# ProDoc_Board3_2025-07-21.net
KiCad netlist of a schematic drawn in EasyEDA Pro
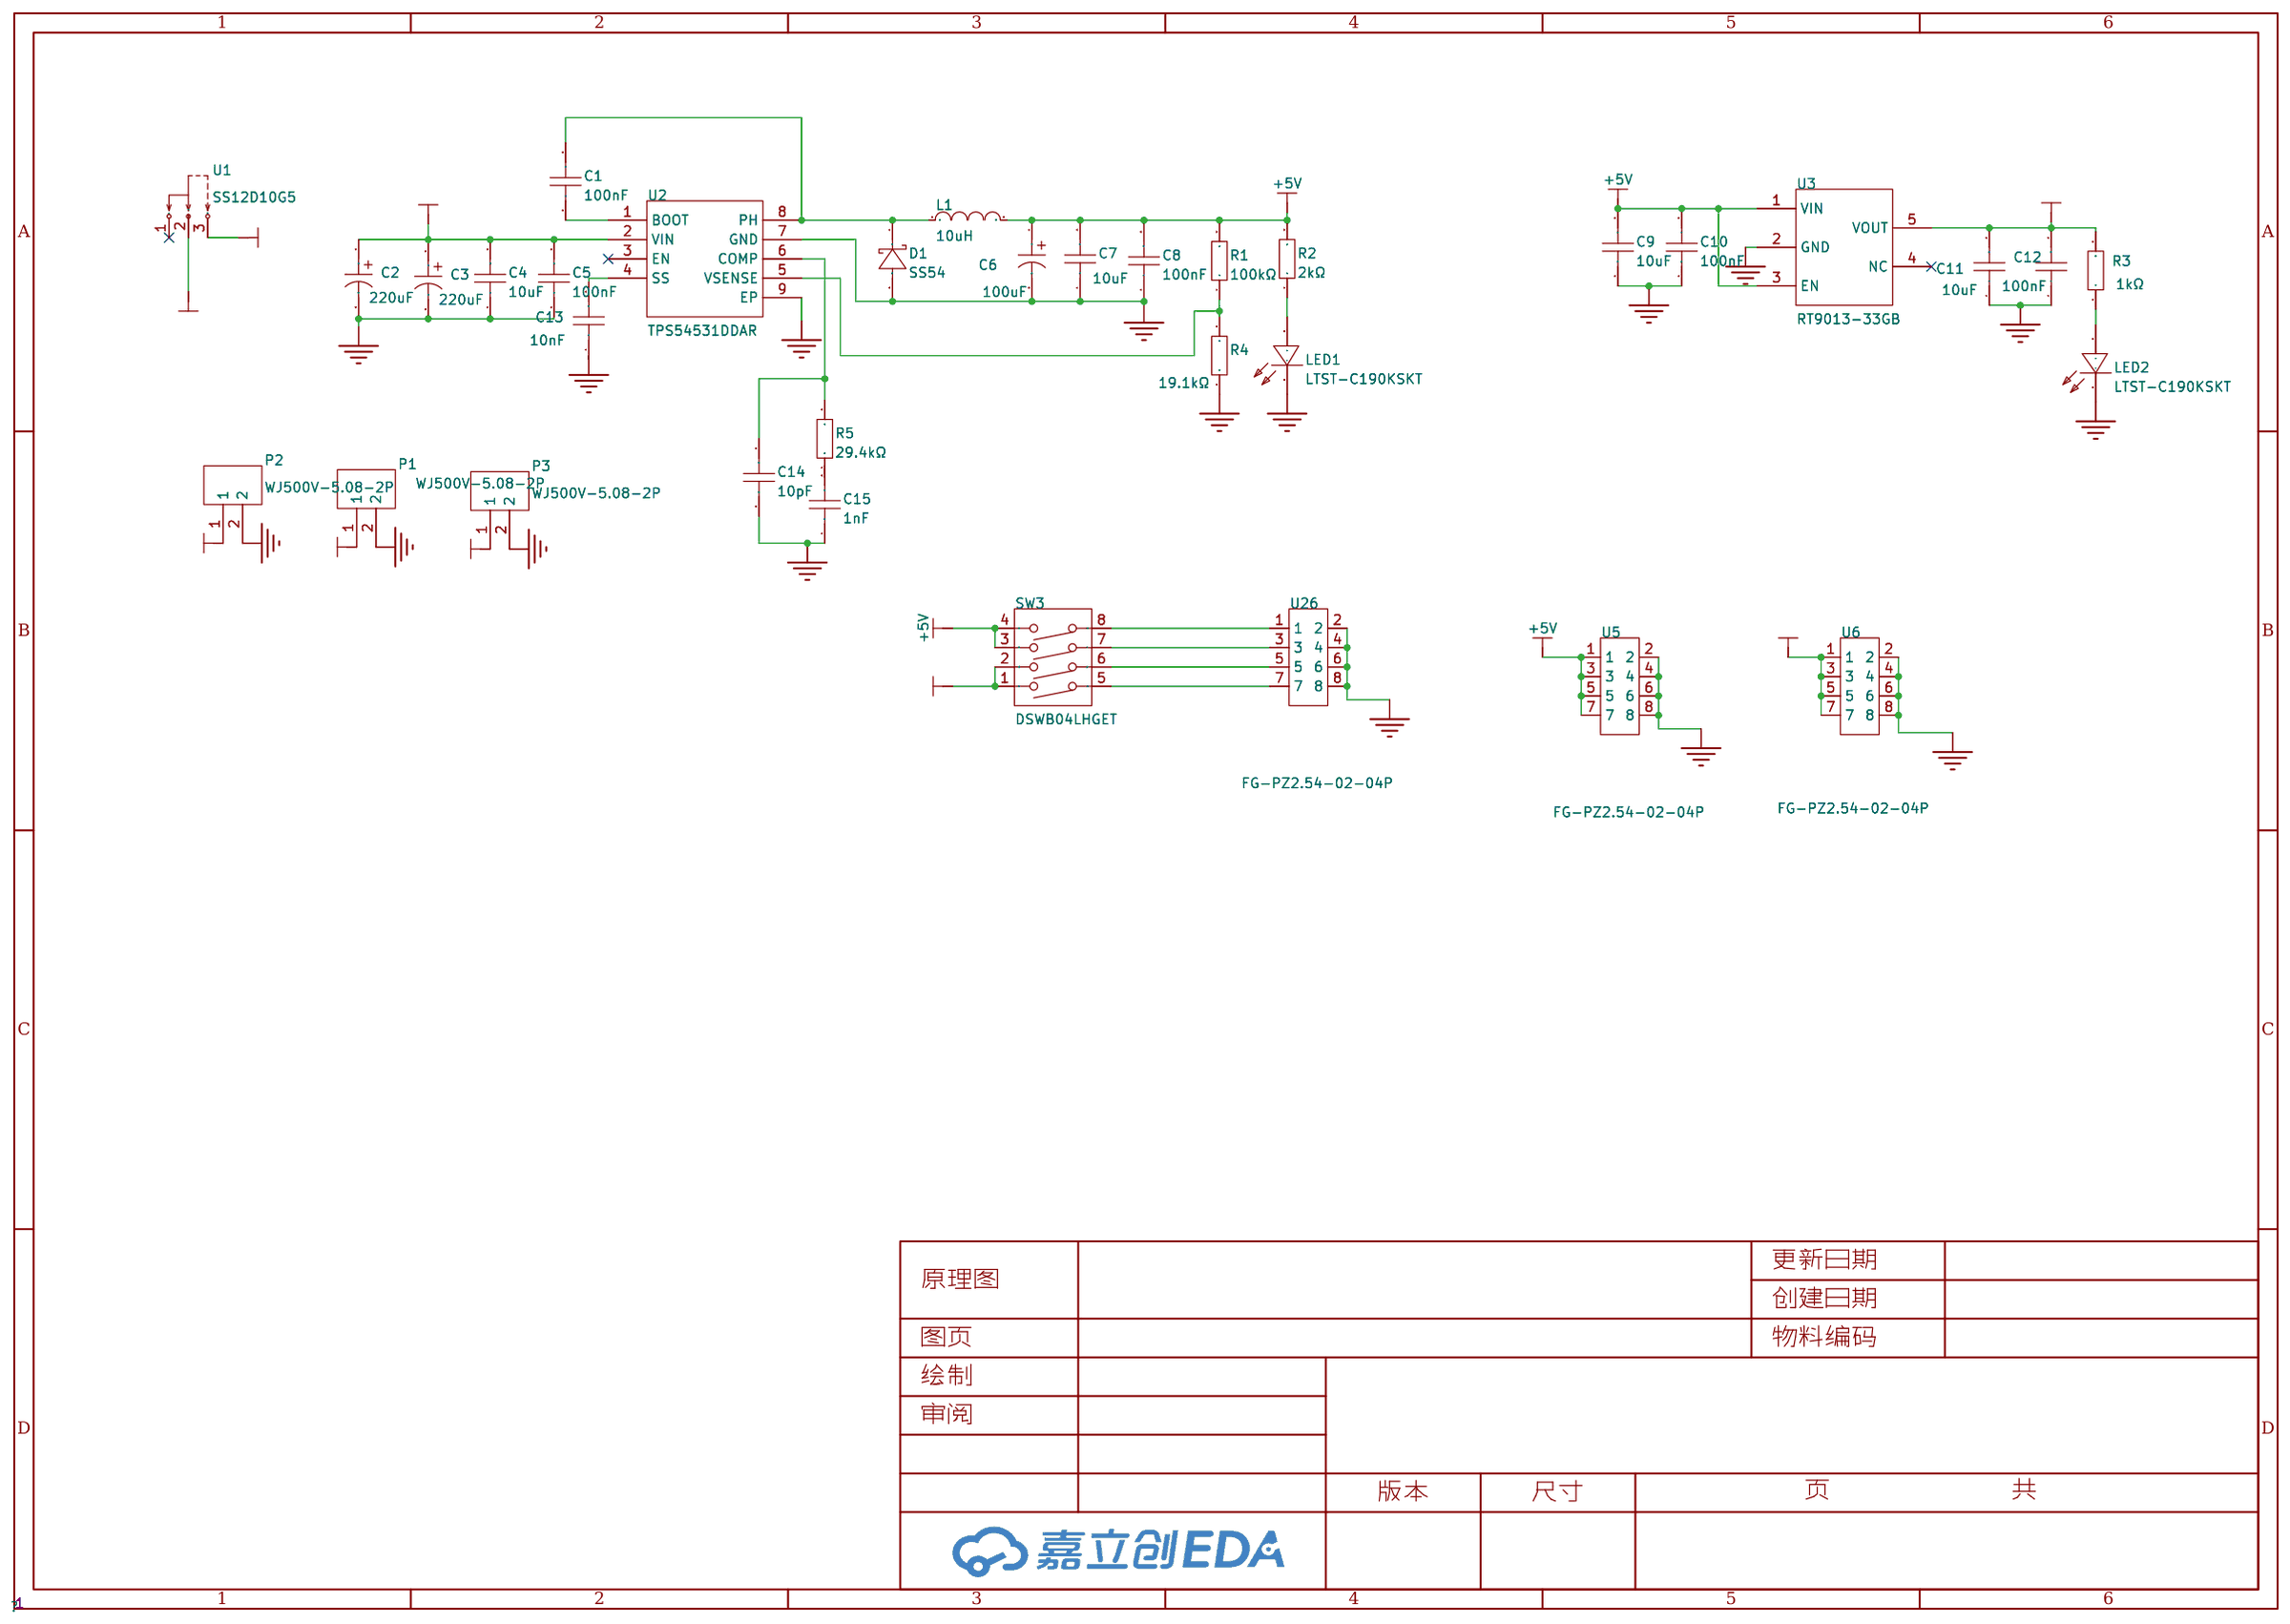
[diagram p0: POWER]
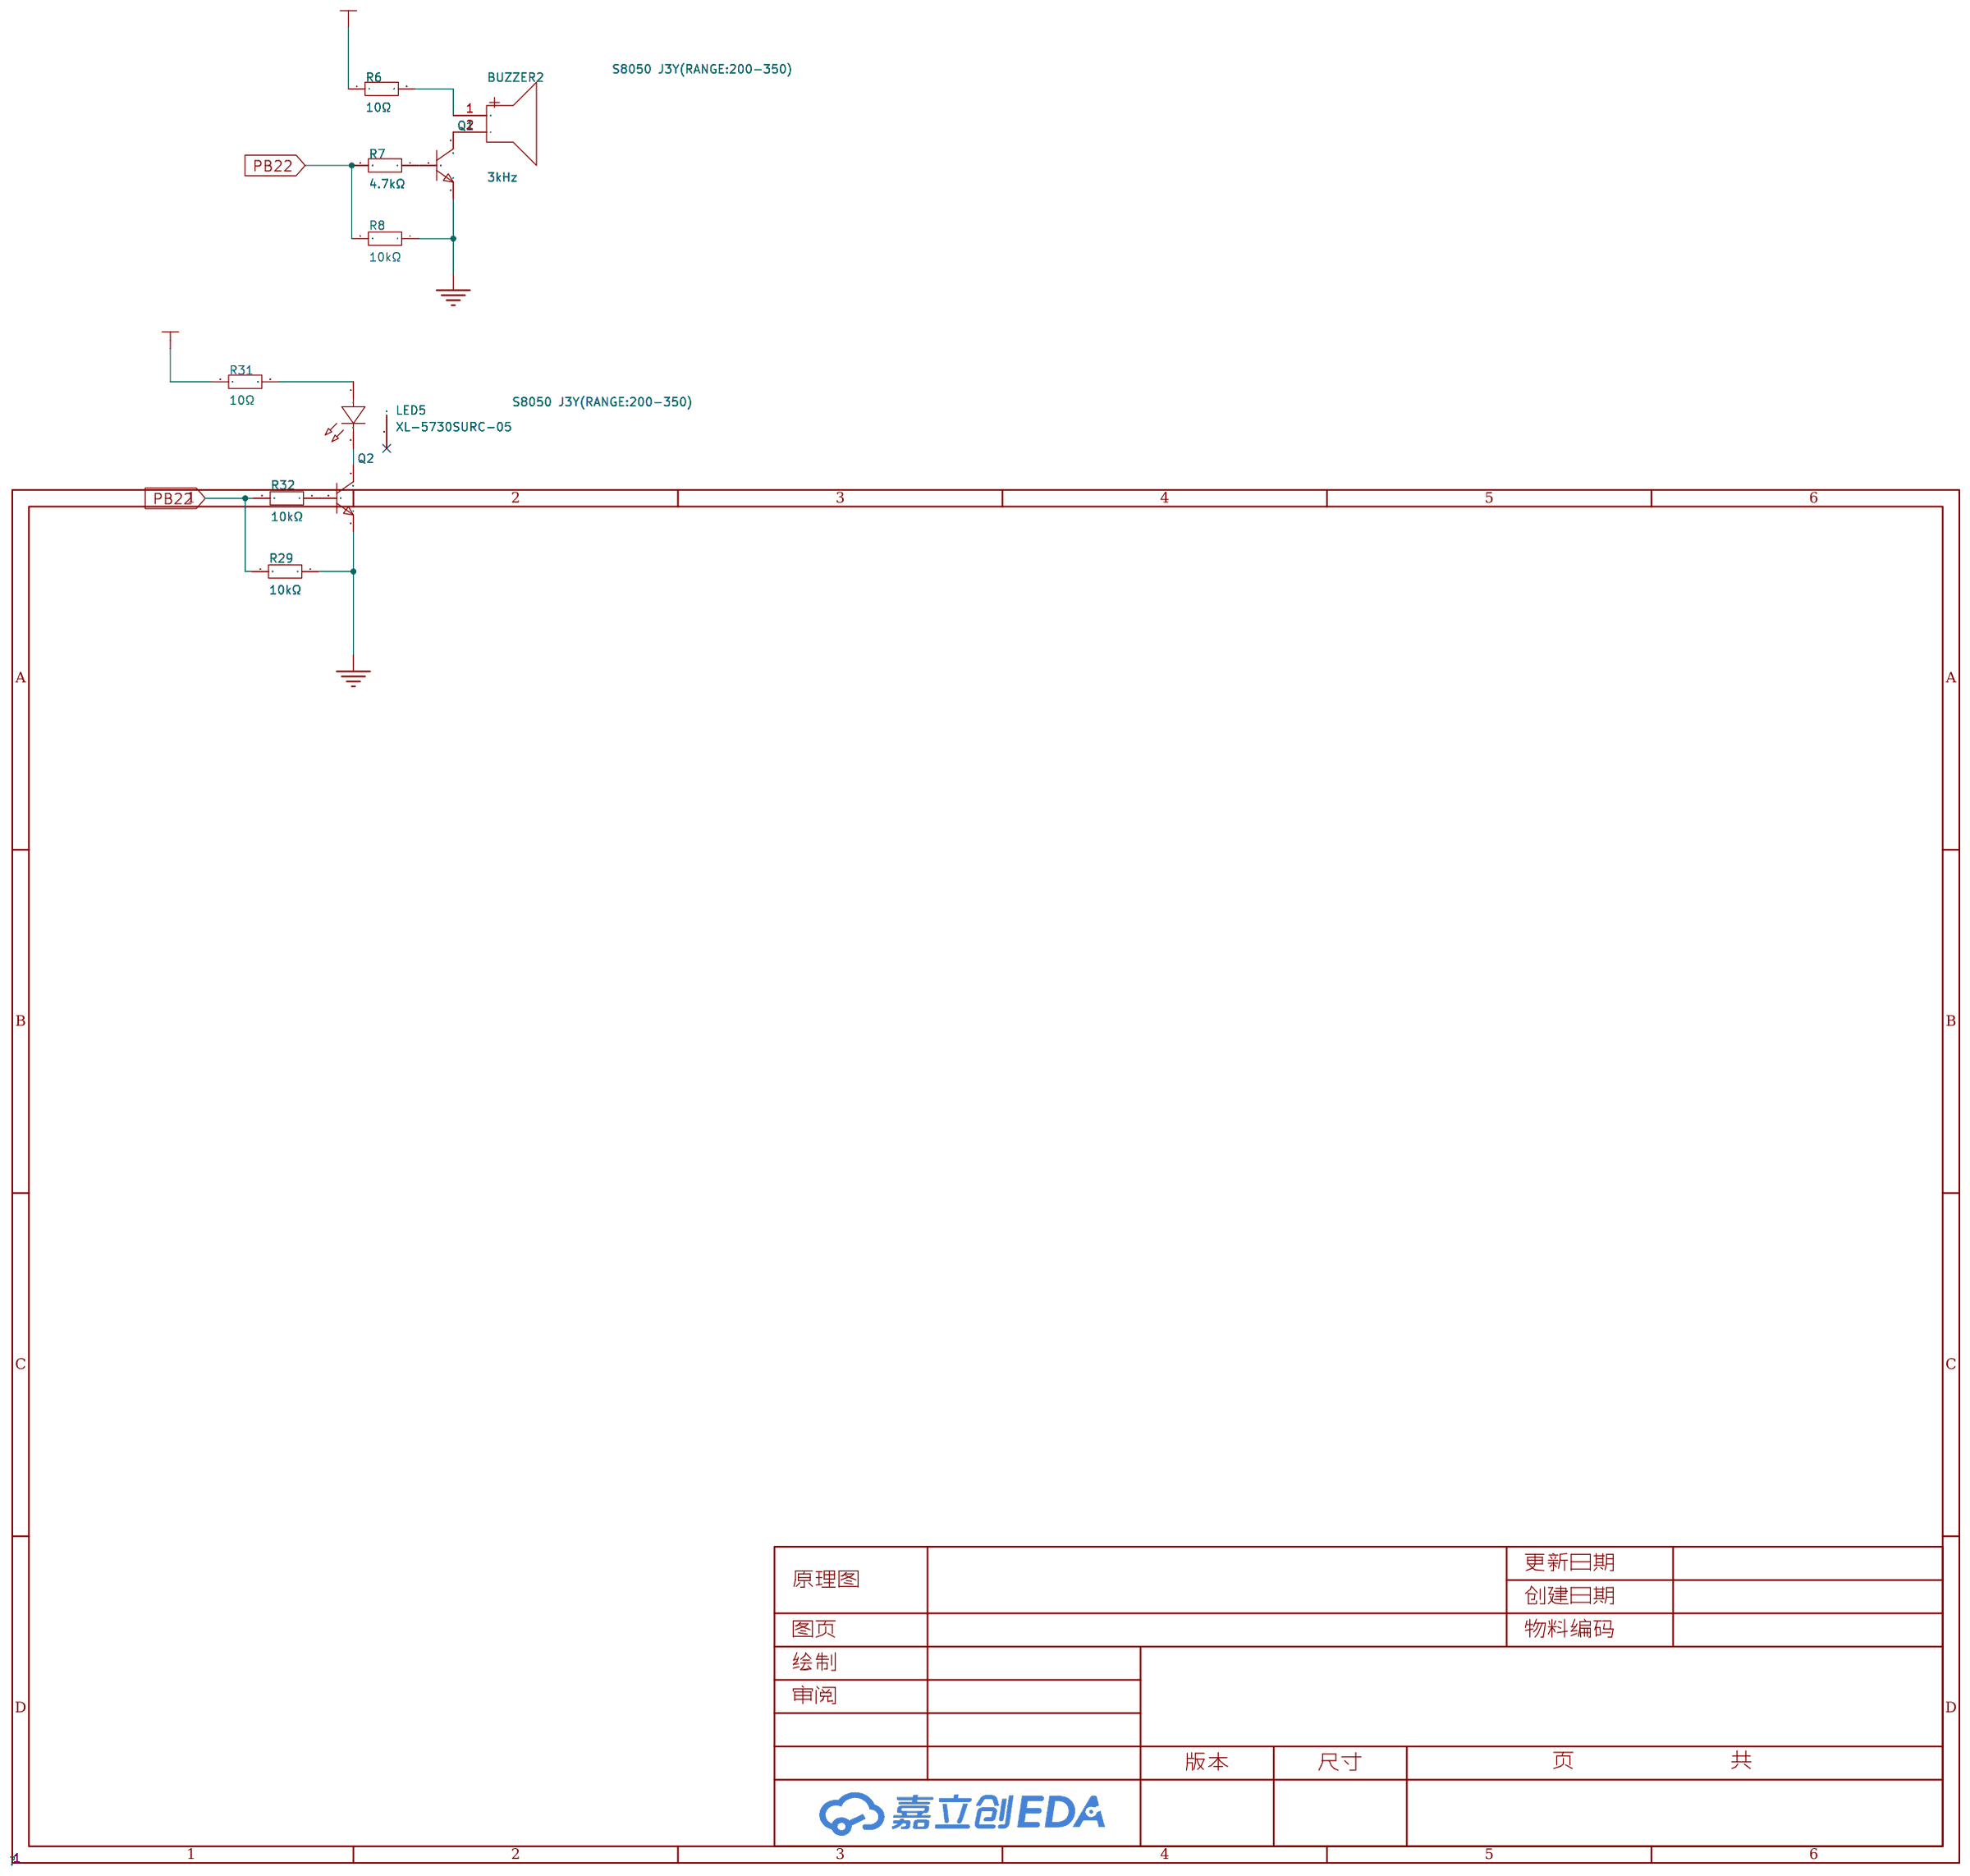
[diagram p1: 器件]
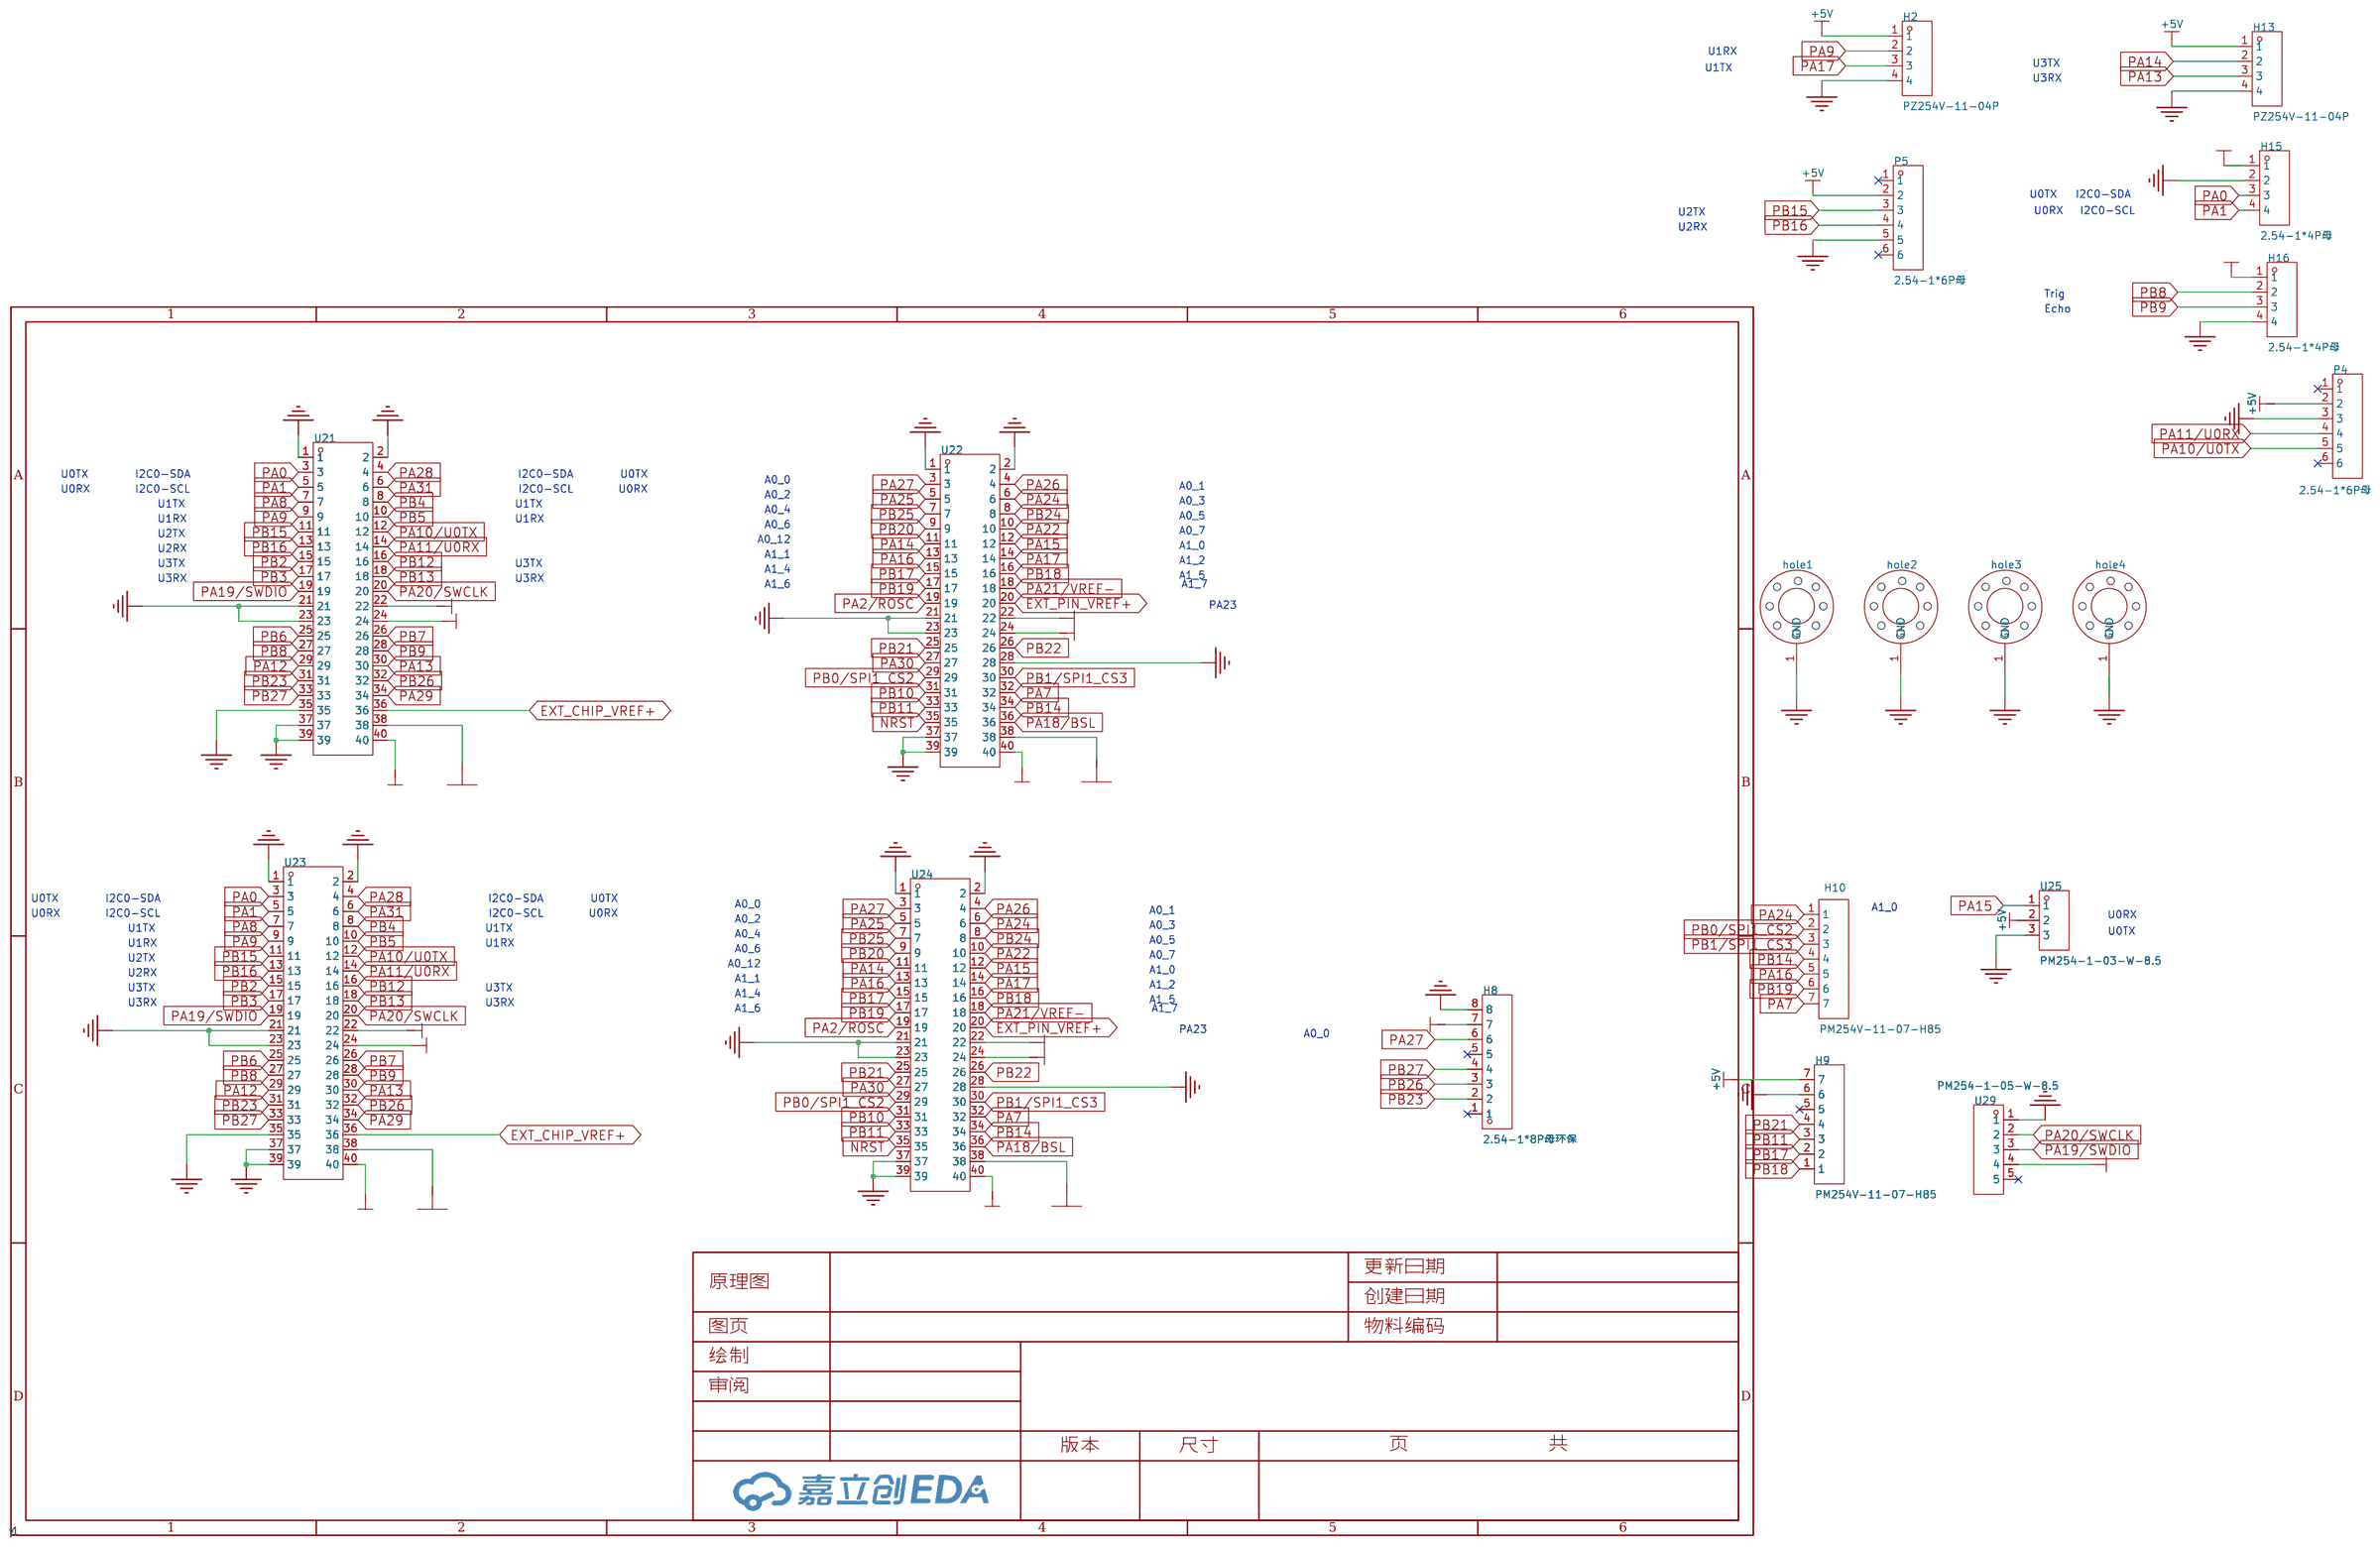
[diagram p2: 连接]

(export (version "E")
  (design (tool "Eeschema 10.0.6"))
  (components
    (comp (ref "C1")
      (value "100nF")
      (fields
        (field (name "Manufacturer Part") "CC0603KRX7R9BB104")
        (field (name "Manufacturer") "YAGEO(国巨)")
      )
      (libsource (lib "easyedapro") (part "CapAcitance"))
    )
    (comp (ref "C2")
      (value "220uF")
      (footprint "easyedapro:CAP-SMD_BD6.3-L6.6-W6.6-LS7.4-FD")
      (description "容值:220uF;精度:±20%;额定电压:25V;纹波电流:150mA@120Hz;等效串联电阻(ESR):-;")
      (fields (field (name "Manufacturer Part") "RVT1E221M0607") (field (name "Manufacturer") "ROQANG(容强)"))
      (libsource (lib "easyedapro") (part "RVT1E221M0607_C2918361"))
    )
    (comp (ref "C3")
      (value "220uF")
      (footprint "easyedapro:CAP-SMD_BD6.3-L6.6-W6.6-LS7.4-FD")
      (description "容值:220uF;精度:±20%;额定电压:25V;纹波电流:150mA@120Hz;等效串联电阻(ESR):-;")
      (fields (field (name "Manufacturer Part") "RVT1E221M0607") (field (name "Manufacturer") "ROQANG(容强)"))
      (libsource (lib "easyedapro") (part "RVT1E221M0607_C2918361"))
    )
    (comp (ref "C4")
      (value "10uF")
      (fields
        (field (name "Manufacturer Part") "CL21A106KAYNNNE")
        (field (name "Manufacturer") "SAMSUNG(三星)")
      )
      (libsource (lib "easyedapro") (part "CapAcitance"))
    )
    (comp (ref "C5")
      (value "100nF")
      (fields
        (field (name "Manufacturer Part") "CC0603KRX7R9BB104")
        (field (name "Manufacturer") "YAGEO(国巨)")
      )
      (libsource (lib "easyedapro") (part "CapAcitance"))
    )
    (comp (ref "C6")
      (value "100uF")
      (footprint "easyedapro:CAP-SMD_BD6.3-L6.6-W6.6-LS7.6-RD")
      (description "容值:100uF;精度:±20%;额定电压:50V;纹波电流:229mA@120Hz;")
      (fields (field (name "Manufacturer Part") "RVT1H101M0607") (field (name "Manufacturer") "ROQANG(容强)"))
      (libsource (lib "easyedapro") (part "RVT1H101M0607"))
    )
    (comp (ref "C7")
      (value "10uF")
      (fields
        (field (name "Manufacturer Part") "CL21A106KAYNNNE")
        (field (name "Manufacturer") "SAMSUNG(三星)")
      )
      (libsource (lib "easyedapro") (part "CapAcitance"))
    )
    (comp (ref "C8")
      (value "100nF")
      (fields
        (field (name "Manufacturer Part") "CC0603KRX7R9BB104")
        (field (name "Manufacturer") "YAGEO(国巨)")
      )
      (libsource (lib "easyedapro") (part "CapAcitance"))
    )
    (comp (ref "C9")
      (value "10uF")
      (fields
        (field (name "Manufacturer Part") "CL21A106KAYNNNE")
        (field (name "Manufacturer") "SAMSUNG(三星)")
      )
      (libsource (lib "easyedapro") (part "CapAcitance"))
    )
    (comp (ref "C10")
      (value "100nF")
      (fields
        (field (name "Manufacturer Part") "CC0603KRX7R9BB104")
        (field (name "Manufacturer") "YAGEO(国巨)")
      )
      (libsource (lib "easyedapro") (part "CapAcitance"))
    )
    (comp (ref "C11")
      (value "10uF")
      (fields
        (field (name "Manufacturer Part") "CL21A106KAYNNNE")
        (field (name "Manufacturer") "SAMSUNG(三星)")
      )
      (libsource (lib "easyedapro") (part "CapAcitance"))
    )
    (comp (ref "C12")
      (value "100nF")
      (fields
        (field (name "Manufacturer Part") "CC0603KRX7R9BB104")
        (field (name "Manufacturer") "YAGEO(国巨)")
      )
      (libsource (lib "easyedapro") (part "CapAcitance"))
    )
    (comp (ref "C13")
      (value "10nF")
      (fields (field (name "Manufacturer Part") "0603B103K500NT") (field (name "Manufacturer") "FH(风华)"))
      (libsource (lib "easyedapro") (part "CapAcitance"))
    )
    (comp (ref "C14")
      (value "10pF")
      (fields
        (field (name "Manufacturer Part") "CL10C100JB8NNNC")
        (field (name "Manufacturer") "SAMSUNG(三星)")
      )
      (libsource (lib "easyedapro") (part "CapAcitance"))
    )
    (comp (ref "C15")
      (value "1nF")
      (fields
        (field (name "Manufacturer Part") "CL10B102KB8NNNC")
        (field (name "Manufacturer") "SAMSUNG(三星)")
      )
      (libsource (lib "easyedapro") (part "CapAcitance"))
    )
    (comp (ref "D1")
      (value "SS54")
      (footprint "easyedapro:SMA_L4.3-W2.6-LS5.0-RD")
      (description "二极管配置:独立式;正向压降(Vf):550mV@5A;直流反向耐压(Vr):40V;整流电流:5A;")
      (fields (field (name "Manufacturer") "TWGMC(台湾迪嘉)"))
      (libsource (lib "easyedapro") (part "SS54_C727065"))
    )
    (comp (ref "L1")
      (value "10uH")
      (footprint "easyedapro:IND-SMD_L7.3-W6.6")
      (description "电感值:10uH;精度:±20%;额定电流:-;饱和电流(Isat):5.5A;类型:一体成型电感;")
      (fields (field (name "Manufacturer Part") "SMMS0630-100M") (field (name "Manufacturer") "SXN(顺翔诺)"))
      (libsource (lib "easyedapro") (part "SMMS0630-100M"))
    )
    (comp (ref "LED1")
      (value "LTST-C190KSKT")
      (footprint "easyedapro:LED0603-RD")
      (fields (field (name "Manufacturer") "LITEON(光宝)"))
      (libsource (lib "easyedapro") (part "LTST-C190KSKT"))
    )
    (comp (ref "LED2")
      (value "LTST-C190KSKT")
      (footprint "easyedapro:LED0603-RD")
      (fields (field (name "Manufacturer") "LITEON(光宝)"))
      (libsource (lib "easyedapro") (part "LTST-C190KSKT"))
    )
    (comp (ref "P1")
      (value "WJ500V-5.08-2P")
      (footprint "easyedapro:CONN-TH_2P-P5.00_WJ500V-5.08-2P")
      (fields (field (name "Manufacturer") "KANGNEX(康奈克斯电气)"))
      (libsource (lib "easyedapro") (part "WJ500V-5.08-2P-14-00A"))
    )
    (comp (ref "P2")
      (value "WJ500V-5.08-2P")
      (footprint "easyedapro:CONN-TH_2P-P5.00_WJ500V-5.08-2P")
      (fields (field (name "Manufacturer") "KANGNEX(康奈克斯电气)"))
      (libsource (lib "easyedapro") (part "WJ500V-5.08-2P-14-00A"))
    )
    (comp (ref "P3")
      (value "WJ500V-5.08-2P")
      (footprint "easyedapro:CONN-TH_2P-P5.00_WJ500V-5.08-2P")
      (fields (field (name "Manufacturer") "KANGNEX(康奈克斯电气)"))
      (libsource (lib "easyedapro") (part "WJ500V-5.08-2P-14-00A"))
    )
    (comp (ref "R1")
      (value "100kΩ")
      (fields
        (field (name "Manufacturer Part") "0603WAF1003T5E")
        (field (name "Manufacturer") "UNI-ROYAL(厚声)")
      )
      (libsource (lib "easyedapro") (part "电阻"))
    )
    (comp (ref "R2")
      (value "2kΩ")
      (fields
        (field (name "Manufacturer Part") "0603WAF2001T5E")
        (field (name "Manufacturer") "UNI-ROYAL(厚声)")
      )
      (libsource (lib "easyedapro") (part "电阻"))
    )
    (comp (ref "R3")
      (value "1kΩ")
      (fields
        (field (name "Manufacturer Part") "0603WAF1001T5E")
        (field (name "Manufacturer") "UNI-ROYAL(厚声)")
      )
      (libsource (lib "easyedapro") (part "电阻"))
    )
    (comp (ref "R4")
      (value "19.1kΩ")
      (fields
        (field (name "Manufacturer Part") "0603WAF1912T5E")
        (field (name "Manufacturer") "UNI-ROYAL(厚声)")
      )
      (libsource (lib "easyedapro") (part "电阻"))
    )
    (comp (ref "R5")
      (value "29.4kΩ")
      (fields (field (name "Manufacturer Part") "FRC0603F2942TS") (field (name "Manufacturer") "FOJAN(富捷)"))
      (libsource (lib "easyedapro") (part "电阻"))
    )
    (comp (ref "SW3")
      (value "DSWB04LHGET")
      (footprint "easyedapro:SW-TH_DSWB04LHGET")
      (description "类型:平拨,凸起式;电路结构:单刀单掷;开关位数:4位;使用寿命:-;颜色:红色;")
      (fields (field (name "Manufacturer") "YE"))
      (libsource (lib "easyedapro") (part "DSWB04LHGET"))
    )
    (comp (ref "U1")
      (value "SS12D10G5")
      (footprint "easyedapro:SW-TH_SHOU-HAN_SS12D10G4")
      (description "电路结构:单刀双掷;安装方式:直插;额定电流(DC):2A;额定电压(DC):125V;机械寿命:3千次;")
      (fields (field (name "Manufacturer") "SHOU HAN(首韩)"))
      (libsource (lib "easyedapro") (part "SS12D10G5"))
    )
    (comp (ref "U2")
      (value "TPS54531DDAR")
      (footprint "easyedapro:SOIC-8_L5.0-W4.0-P1.27-LS6.0-BL-EP2.0")
      (description "功能类型:降压型;输出类型:可调;工作电压:3.5V~28V;输出电压:-;输出电流:5A;")
      (fields (field (name "Manufacturer") "TI(德州仪器)"))
      (libsource (lib "easyedapro") (part "TPS54531DDAR"))
    )
    (comp (ref "U3")
      (value "RT9013-33GB")
      (footprint "easyedapro:SOT-23-5_L3.0-W1.7-P0.95-LS2.8-BL")
      (description "输出类型:固定;最大输入电压:5.5V;输出电压:3.3V;输出电流:500mA;电源纹波抑制比(PSRR):50dB@(10kHz);输出极性:正极;")
      (fields (field (name "Manufacturer") "RICHTEK(立锜)"))
      (libsource (lib "easyedapro") (part "RT9013-33GB"))
    )
    (comp (ref "U5")
      (value "FG-PZ2.54-02-04P")
      (footprint "easyedapro:HDR-TH_8P-P2.54-V-M-R2-C4-S2.54")
      (description "插针结构:2x4P;间距:2.54mm;圆针/方针:方针;排数:双排;")
      (fields (field (name "Manufacturer") "FG(富港)"))
      (libsource (lib "easyedapro") (part "FG-PZ2.54-02-04P"))
    )
    (comp (ref "U6")
      (value "FG-PZ2.54-02-04P")
      (footprint "easyedapro:HDR-TH_8P-P2.54-V-M-R2-C4-S2.54")
      (description "插针结构:2x4P;间距:2.54mm;圆针/方针:方针;排数:双排;")
      (fields (field (name "Manufacturer") "FG(富港)"))
      (libsource (lib "easyedapro") (part "FG-PZ2.54-02-04P"))
    )
    (comp (ref "U26")
      (value "FG-PZ2.54-02-04P")
      (footprint "easyedapro:HDR-TH_8P-P2.54-V-M-R2-C4-S2.54")
      (description "插针结构:2x4P;间距:2.54mm;圆针/方针:方针;排数:双排;")
      (fields (field (name "Manufacturer") "FG(富港)"))
      (libsource (lib "easyedapro") (part "FG-PZ2.54-02-04P"))
    )
    (comp (ref "BUZZER2")
      (value "3kHz")
      (footprint "easyedapro:BUZ-TH_BD9.0-P5.00-D0.6-FD")
      (description "驱动方式:有源(内含驱动线路);构造类型:电磁式;频率:3kHz;声压(SPL):85dB;")
      (fields (field (name "Manufacturer Part") "HNB09A03") (field (name "Manufacturer") "华能"))
      (libsource (lib "easyedapro") (part "HNB09A03"))
    )
    (comp (ref "LED5")
      (value "XL-5730SURC-05")
      (footprint "easyedapro:LED-SMD_XL-5730SURC-05")
      (fields (field (name "Manufacturer") "XINGLIGHT(成兴光)"))
      (libsource (lib "easyedapro") (part "XL-5730SURC-05"))
    )
    (comp (ref "Q1")
      (value "S8050 J3Y(RANGE:200-350)")
      (footprint "easyedapro:SOT-23-3_L3.0-W1.7-P0.95-LS2.9-BR")
      (description "晶体管类型:NPN;集电极电流(Ic):500mA;集射极击穿电压(Vceo):25V;耗散功率(Pd):300mW;直流电流增益(hFE):200@500mA,1V;")
      (fields (field (name "Manufacturer") "CJ(江苏长电/长晶)"))
      (libsource (lib "easyedapro") (part "S8050_C2146"))
    )
    (comp (ref "Q2")
      (value "S8050 J3Y(RANGE:200-350)")
      (footprint "easyedapro:SOT-23-3_L3.0-W1.7-P0.95-LS2.9-BR")
      (description "晶体管类型:NPN;集电极电流(Ic):500mA;集射极击穿电压(Vceo):25V;耗散功率(Pd):300mW;直流电流增益(hFE):200@500mA,1V;")
      (fields (field (name "Manufacturer") "CJ(江苏长电/长晶)"))
      (libsource (lib "easyedapro") (part "S8050_C2146"))
    )
    (comp (ref "R6")
      (value "10Ω")
      (footprint "easyedapro:R0603")
      (description "电阻类型:厚膜电阻;阻值:10Ω;精度:±1%;功率:100mW;最大工作电压:75V;温度系数:±400ppm/°C;")
      (fields
        (field (name "Manufacturer Part") "0603WAF100JT5E")
        (field (name "Manufacturer") "UNI-ROYAL(厚声)")
      )
      (libsource (lib "easyedapro") (part "0603WAF100JT5E"))
    )
    (comp (ref "R7")
      (value "4.7kΩ")
      (footprint "easyedapro:R0603")
      (description "电阻类型:厚膜电阻;阻值:4.7kΩ;精度:±1%;功率:100mW;最大工作电压:75V;温度系数:±100ppm/°C;")
      (fields
        (field (name "Manufacturer Part") "0603WAF4701T5E")
        (field (name "Manufacturer") "UNI-ROYAL(厚声)")
      )
      (libsource (lib "easyedapro") (part "0603WAF4701T5E"))
    )
    (comp (ref "R8")
      (value "10kΩ")
      (footprint "easyedapro:R0603")
      (description "电阻类型:厚膜电阻;阻值:10kΩ;精度:±1%;功率:100mW;工作电压:75V;温度系数:±100ppm/℃;")
      (fields
        (field (name "Manufacturer Part") "0603WAF1002T5E")
        (field (name "Manufacturer") "UNI-ROYAL(厚声)")
      )
      (libsource (lib "easyedapro") (part "0603WAF1001T5E"))
    )
    (comp (ref "R29")
      (value "10kΩ")
      (footprint "easyedapro:R0603")
      (description "电阻类型:厚膜电阻;阻值:10kΩ;精度:±1%;功率:100mW;工作电压:75V;温度系数:±100ppm/℃;")
      (fields
        (field (name "Manufacturer Part") "0603WAF1002T5E")
        (field (name "Manufacturer") "UNI-ROYAL(厚声)")
      )
      (libsource (lib "easyedapro") (part "0603WAF1001T5E"))
    )
    (comp (ref "R31")
      (value "10Ω")
      (footprint "easyedapro:R0603")
      (description "电阻类型:厚膜电阻;阻值:10Ω;精度:±1%;功率:100mW;最大工作电压:75V;温度系数:±400ppm/°C;")
      (fields
        (field (name "Manufacturer Part") "0603WAF100JT5E")
        (field (name "Manufacturer") "UNI-ROYAL(厚声)")
      )
      (libsource (lib "easyedapro") (part "0603WAF100JT5E"))
    )
    (comp (ref "R32")
      (value "10kΩ")
      (footprint "easyedapro:R0603")
      (description "电阻类型:厚膜电阻;阻值:10kΩ;精度:±1%;功率:100mW;工作电压:75V;温度系数:±100ppm/℃;")
      (fields
        (field (name "Manufacturer Part") "0603WAF1002T5E")
        (field (name "Manufacturer") "UNI-ROYAL(厚声)")
      )
      (libsource (lib "easyedapro") (part "0603WAF1001T5E"))
    )
    (comp (ref "H2")
      (value "PZ254V-11-04P")
      (footprint "easyedapro:HDR-TH_4P-P2.54-V-M")
      (fields (field (name "Manufacturer") "XFCN(兴飞)"))
      (libsource (lib "easyedapro") (part "PZ254V-11-04P_C2691448"))
    )
    (comp (ref "H8")
      (value "2.54-1*8P母环保")
      (fields (field (name "Manufacturer") "BOOMELE(博穆精密)"))
      (libsource (lib "easyedapro") (part "PZ254V-11-08P"))
    )
    (comp (ref "H9")
      (value "PM254V-11-07-H85")
      (fields (field (name "Manufacturer") "XFCN(兴飞)"))
      (libsource (lib "easyedapro") (part "PZ254V-11-07P"))
    )
    (comp (ref "H10")
      (value "PM254V-11-07-H85")
      (fields (field (name "Manufacturer") "XFCN(兴飞)"))
      (libsource (lib "easyedapro") (part "PZ254V-11-07P"))
    )
    (comp (ref "H13")
      (value "PZ254V-11-04P")
      (footprint "easyedapro:HDR-TH_4P-P2.54-V-M")
      (fields (field (name "Manufacturer") "XFCN(兴飞)"))
      (libsource (lib "easyedapro") (part "PZ254V-11-04P_C2691448"))
    )
    (comp (ref "H15")
      (value "2.54-1*4P母")
      (footprint "easyedapro:HDR-TH_4P-P2.54-V-F")
      (fields (field (name "Manufacturer") "BOOMELE(博穆精密)"))
      (libsource (lib "easyedapro") (part "2.54-1*4P母"))
    )
    (comp (ref "H16")
      (value "2.54-1*4P母")
      (footprint "easyedapro:HDR-TH_4P-P2.54-V-F")
      (fields (field (name "Manufacturer") "BOOMELE(博穆精密)"))
      (libsource (lib "easyedapro") (part "2.54-1*4P母"))
    )
    (comp (ref "hole1")
      (value "M3")
      (footprint "easyedapro:m3 125x300")
      (description "梅花螺丝孔")
      (libsource (lib "easyedapro") (part "m3_梅花螺丝孔"))
    )
    (comp (ref "hole2")
      (value "M3")
      (footprint "easyedapro:m3 125x300")
      (description "梅花螺丝孔")
      (libsource (lib "easyedapro") (part "m3_梅花螺丝孔"))
    )
    (comp (ref "hole3")
      (value "M3")
      (footprint "easyedapro:m3 125x300")
      (description "梅花螺丝孔")
      (libsource (lib "easyedapro") (part "m3_梅花螺丝孔"))
    )
    (comp (ref "hole4")
      (value "M3")
      (footprint "easyedapro:m3 125x300")
      (description "梅花螺丝孔")
      (libsource (lib "easyedapro") (part "m3_梅花螺丝孔"))
    )
    (comp (ref "P4")
      (value "2.54-1*6P母")
      (footprint "easyedapro:HDR-TH_6P-P2.54-V-F")
      (description "插孔结构:1x6P;间距:2.54mm;行距:-;安装类型:直插;排数:单排;总孔位数:6P;塑高:-;触头材质:-;触头镀层:-;")
      (fields (field (name "Manufacturer") "BOOMELE(博穆精密)"))
      (libsource (lib "easyedapro") (part "Header-Female-2.54_1x6"))
    )
    (comp (ref "P5")
      (value "2.54-1*6P母")
      (footprint "easyedapro:HDR-TH_6P-P2.54-V-F")
      (description "插孔结构:1x6P;间距:2.54mm;行距:-;安装类型:直插;排数:单排;总孔位数:6P;塑高:-;触头材质:-;触头镀层:-;")
      (fields (field (name "Manufacturer") "BOOMELE(博穆精密)"))
      (libsource (lib "easyedapro") (part "Header-Female-2.54_1x6"))
    )
    (comp (ref "U21")
      (value "2.54-2*20")
      (footprint "easyedapro:HDR-TH_40P-P2.54-V-M-R2-C20-S2.54")
      (description "插针结构:2x20P;间距:2.54mm;安装类型:直插;排数:双排;总PIN位数:40P;触头镀层:金;")
      (fields (field (name "Manufacturer") "ZHOURI(洲日)"))
      (libsource (lib "easyedapro") (part "PZ2.54-2*20"))
    )
    (comp (ref "U22")
      (value "2.54-2*20")
      (footprint "easyedapro:HDR-TH_40P-P2.54-V-M-R2-C20-S2.54")
      (description "插针结构:2x20P;间距:2.54mm;安装类型:直插;排数:双排;总PIN位数:40P;触头镀层:金;")
      (fields (field (name "Manufacturer") "ZHOURI(洲日)"))
      (libsource (lib "easyedapro") (part "PZ2.54-2*20"))
    )
    (comp (ref "U23")
      (value "PZ2.54-2*20")
      (footprint "easyedapro:HDR-TH_40P-P2.54-V-M-R2-C20-S2.54")
      (description "插针结构:2x20P;间距:2.54mm;安装类型:直插;排数:双排;总PIN位数:40P;触头镀层:金;")
      (fields (field (name "Manufacturer") "ZHOURI(洲日)"))
      (libsource (lib "easyedapro") (part "PZ2.54-2*20"))
    )
    (comp (ref "U24")
      (value "PZ2.54-2*20")
      (footprint "easyedapro:HDR-TH_40P-P2.54-V-M-R2-C20-S2.54")
      (description "插针结构:2x20P;间距:2.54mm;安装类型:直插;排数:双排;总PIN位数:40P;触头镀层:金;")
      (fields (field (name "Manufacturer") "ZHOURI(洲日)"))
      (libsource (lib "easyedapro") (part "PZ2.54-2*20"))
    )
    (comp (ref "U25")
      (value "PM254-1-03-W-8.5")
      (footprint "easyedapro:HDR-TH_3P-P2.54-H-F-W10.0-N")
      (fields (field (name "Manufacturer") "HCTL(华灿天禄)"))
      (libsource (lib "easyedapro") (part "PM254-1-03-W-8.5"))
    )
    (comp (ref "U29")
      (value "PM254-1-05-W-8.5")
      (footprint "easyedapro:HDR-TH_5P-P2.54-H-F-W10.0-N")
      (fields (field (name "Manufacturer") "HCTL(华灿天禄)"))
      (libsource (lib "easyedapro") (part "PM254-1-05-W-8.5"))
    )
  )
  (nets
    (net (code "1") (name "+5V") (class "Default")
      (node (ref "C10") (pin "2") (pinfunction "2_2") (pintype "input"))
      (node (ref "C6") (pin "1") (pinfunction "1_1") (pintype "input"))
      (node (ref "C7") (pin "2") (pinfunction "2_2") (pintype "input"))
      (node (ref "C8") (pin "2") (pinfunction "2_2") (pintype "input"))
      (node (ref "C9") (pin "2") (pinfunction "2_2") (pintype "input"))
      (node (ref "H13") (pin "1") (pinfunction "1_1") (pintype "unspecified"))
      (node (ref "H15") (pin "1") (pinfunction "1_1") (pintype "unspecified"))
      (node (ref "H16") (pin "1") (pinfunction "1_1") (pintype "unspecified"))
      (node (ref "H2") (pin "1") (pinfunction "1_1") (pintype "unspecified"))
      (node (ref "H8") (pin "7") (pinfunction "7_7") (pintype "unspecified"))
      (node (ref "H9") (pin "7") (pinfunction "7_7") (pintype "unspecified"))
      (node (ref "L1") (pin "2") (pinfunction "2_2") (pintype "unspecified"))
      (node (ref "P4") (pin "2") (pinfunction "2_2") (pintype "unspecified"))
      (node (ref "P5") (pin "2") (pinfunction "2_2") (pintype "unspecified"))
      (node (ref "R1") (pin "2") (pinfunction "2_2") (pintype "input"))
      (node (ref "R2") (pin "2") (pinfunction "2_2") (pintype "input"))
      (node (ref "SW3") (pin "3") (pinfunction "3_3") (pintype "unspecified"))
      (node (ref "SW3") (pin "4") (pinfunction "4_4") (pintype "unspecified"))
      (node (ref "U21") (pin "24") (pinfunction "24_24") (pintype "unspecified"))
      (node (ref "U21") (pin "40") (pinfunction "40_40") (pintype "unspecified"))
      (node (ref "U22") (pin "24") (pinfunction "24_24") (pintype "unspecified"))
      (node (ref "U22") (pin "40") (pinfunction "40_40") (pintype "unspecified"))
      (node (ref "U23") (pin "24") (pinfunction "24_24") (pintype "unspecified"))
      (node (ref "U23") (pin "40") (pinfunction "40_40") (pintype "unspecified"))
      (node (ref "U24") (pin "24") (pinfunction "24_24") (pintype "unspecified"))
      (node (ref "U24") (pin "40") (pinfunction "40_40") (pintype "unspecified"))
      (node (ref "U25") (pin "2") (pinfunction "2_2") (pintype "unspecified"))
      (node (ref "U3") (pin "1") (pinfunction "VIN_1") (pintype "unspecified"))
      (node (ref "U3") (pin "3") (pinfunction "EN_3") (pintype "unspecified"))
      (node (ref "U5") (pin "1") (pinfunction "1_1") (pintype "unspecified"))
      (node (ref "U5") (pin "3") (pinfunction "3_3") (pintype "unspecified"))
      (node (ref "U5") (pin "5") (pinfunction "5_5") (pintype "unspecified"))
      (node (ref "U5") (pin "7") (pinfunction "7_7") (pintype "unspecified"))
    )
    (net (code "2") (name "3V3") (class "Default")
      (node (ref "C11") (pin "2") (pinfunction "2_2") (pintype "input"))
      (node (ref "C12") (pin "2") (pinfunction "2_2") (pintype "input"))
      (node (ref "R3") (pin "2") (pinfunction "2_2") (pintype "input"))
      (node (ref "R31") (pin "1") (pinfunction "1_1") (pintype "input"))
      (node (ref "R6") (pin "1") (pinfunction "1_1") (pintype "input"))
      (node (ref "SW3") (pin "1") (pinfunction "1_1") (pintype "unspecified"))
      (node (ref "SW3") (pin "2") (pinfunction "2_2") (pintype "unspecified"))
      (node (ref "U21") (pin "22") (pinfunction "22_22") (pintype "unspecified"))
      (node (ref "U21") (pin "38") (pinfunction "38_38") (pintype "unspecified"))
      (node (ref "U22") (pin "22") (pinfunction "22_22") (pintype "unspecified"))
      (node (ref "U22") (pin "38") (pinfunction "38_38") (pintype "unspecified"))
      (node (ref "U23") (pin "22") (pinfunction "22_22") (pintype "unspecified"))
      (node (ref "U23") (pin "38") (pinfunction "38_38") (pintype "unspecified"))
      (node (ref "U24") (pin "22") (pinfunction "22_22") (pintype "unspecified"))
      (node (ref "U24") (pin "38") (pinfunction "38_38") (pintype "unspecified"))
      (node (ref "U29") (pin "4") (pinfunction "4_4") (pintype "unspecified"))
      (node (ref "U3") (pin "5") (pinfunction "VOUT_5") (pintype "unspecified"))
      (node (ref "U6") (pin "1") (pinfunction "1_1") (pintype "unspecified"))
      (node (ref "U6") (pin "3") (pinfunction "3_3") (pintype "unspecified"))
      (node (ref "U6") (pin "5") (pinfunction "5_5") (pintype "unspecified"))
      (node (ref "U6") (pin "7") (pinfunction "7_7") (pintype "unspecified"))
    )
    (net (code "3") (name "EXT_CHIP_VREF+") (class "Default")
      (node (ref "U21") (pin "36") (pinfunction "36_36") (pintype "unspecified"))
      (node (ref "U23") (pin "36") (pinfunction "36_36") (pintype "unspecified"))
    )
    (net (code "4") (name "EXT_PIN_VREF+") (class "Default")
      (node (ref "U22") (pin "20") (pinfunction "20_20") (pintype "unspecified"))
      (node (ref "U24") (pin "20") (pinfunction "20_20") (pintype "unspecified"))
    )
    (net (code "5") (name "GND") (class "Default")
      (node (ref "C10") (pin "1") (pinfunction "1_1") (pintype "input"))
      (node (ref "C11") (pin "1") (pinfunction "1_1") (pintype "input"))
      (node (ref "C12") (pin "1") (pinfunction "1_1") (pintype "input"))
      (node (ref "C13") (pin "1") (pinfunction "1_1") (pintype "input"))
      (node (ref "C14") (pin "1") (pinfunction "1_1") (pintype "input"))
      (node (ref "C15") (pin "1") (pinfunction "1_1") (pintype "input"))
      (node (ref "C2") (pin "2") (pinfunction "2_2") (pintype "input"))
      (node (ref "C3") (pin "2") (pinfunction "2_2") (pintype "input"))
      (node (ref "C4") (pin "1") (pinfunction "1_1") (pintype "input"))
      (node (ref "C5") (pin "1") (pinfunction "1_1") (pintype "input"))
      (node (ref "C6") (pin "2") (pinfunction "2_2") (pintype "input"))
      (node (ref "C7") (pin "1") (pinfunction "1_1") (pintype "input"))
      (node (ref "C8") (pin "1") (pinfunction "1_1") (pintype "input"))
      (node (ref "C9") (pin "1") (pinfunction "1_1") (pintype "input"))
      (node (ref "D1") (pin "2") (pinfunction "2_2") (pintype "unspecified"))
      (node (ref "H13") (pin "4") (pinfunction "4_4") (pintype "unspecified"))
      (node (ref "H15") (pin "2") (pinfunction "2_2") (pintype "unspecified"))
      (node (ref "H16") (pin "4") (pinfunction "4_4") (pintype "unspecified"))
      (node (ref "H2") (pin "4") (pinfunction "4_4") (pintype "unspecified"))
      (node (ref "H8") (pin "8") (pinfunction "8_8") (pintype "unspecified"))
      (node (ref "H9") (pin "6") (pinfunction "6_6") (pintype "unspecified"))
      (node (ref "LED1") (pin "1") (pinfunction "-_1") (pintype "unspecified"))
      (node (ref "LED2") (pin "1") (pinfunction "-_1") (pintype "unspecified"))
      (node (ref "P1") (pin "2") (pinfunction "2_2") (pintype "unspecified"))
      (node (ref "P2") (pin "2") (pinfunction "2_2") (pintype "unspecified"))
      (node (ref "P3") (pin "2") (pinfunction "2_2") (pintype "unspecified"))
      (node (ref "P4") (pin "3") (pinfunction "3_3") (pintype "unspecified"))
      (node (ref "P5") (pin "5") (pinfunction "5_5") (pintype "unspecified"))
      (node (ref "Q1") (pin "2") (pinfunction "E_2") (pintype "unspecified"))
      (node (ref "Q2") (pin "2") (pinfunction "E_2") (pintype "unspecified"))
      (node (ref "R29") (pin "1") (pinfunction "1_1") (pintype "input"))
      (node (ref "R4") (pin "1") (pinfunction "1_1") (pintype "input"))
      (node (ref "R8") (pin "1") (pinfunction "1_1") (pintype "input"))
      (node (ref "U2") (pin "7") (pinfunction "GND_7") (pintype "unspecified"))
      (node (ref "U2") (pin "9") (pinfunction "EP_9") (pintype "unspecified"))
      (node (ref "U21") (pin "1") (pinfunction "1_1") (pintype "unspecified"))
      (node (ref "U21") (pin "2") (pinfunction "2_2") (pintype "unspecified"))
      (node (ref "U21") (pin "21") (pinfunction "21_21") (pintype "unspecified"))
      (node (ref "U21") (pin "23") (pinfunction "23_23") (pintype "unspecified"))
      (node (ref "U21") (pin "35") (pinfunction "35_35") (pintype "unspecified"))
      (node (ref "U21") (pin "37") (pinfunction "37_37") (pintype "unspecified"))
      (node (ref "U21") (pin "39") (pinfunction "39_39") (pintype "unspecified"))
      (node (ref "U22") (pin "1") (pinfunction "1_1") (pintype "unspecified"))
      (node (ref "U22") (pin "2") (pinfunction "2_2") (pintype "unspecified"))
      (node (ref "U22") (pin "21") (pinfunction "21_21") (pintype "unspecified"))
      (node (ref "U22") (pin "23") (pinfunction "23_23") (pintype "unspecified"))
      (node (ref "U22") (pin "28") (pinfunction "28_28") (pintype "unspecified"))
      (node (ref "U22") (pin "37") (pinfunction "37_37") (pintype "unspecified"))
      (node (ref "U22") (pin "39") (pinfunction "39_39") (pintype "unspecified"))
      (node (ref "U23") (pin "1") (pinfunction "1_1") (pintype "unspecified"))
      (node (ref "U23") (pin "2") (pinfunction "2_2") (pintype "unspecified"))
      (node (ref "U23") (pin "21") (pinfunction "21_21") (pintype "unspecified"))
      (node (ref "U23") (pin "23") (pinfunction "23_23") (pintype "unspecified"))
      (node (ref "U23") (pin "35") (pinfunction "35_35") (pintype "unspecified"))
      (node (ref "U23") (pin "37") (pinfunction "37_37") (pintype "unspecified"))
      (node (ref "U23") (pin "39") (pinfunction "39_39") (pintype "unspecified"))
      (node (ref "U24") (pin "1") (pinfunction "1_1") (pintype "unspecified"))
      (node (ref "U24") (pin "2") (pinfunction "2_2") (pintype "unspecified"))
      (node (ref "U24") (pin "21") (pinfunction "21_21") (pintype "unspecified"))
      (node (ref "U24") (pin "23") (pinfunction "23_23") (pintype "unspecified"))
      (node (ref "U24") (pin "28") (pinfunction "28_28") (pintype "unspecified"))
      (node (ref "U24") (pin "37") (pinfunction "37_37") (pintype "unspecified"))
      (node (ref "U24") (pin "39") (pinfunction "39_39") (pintype "unspecified"))
      (node (ref "U25") (pin "3") (pinfunction "3_3") (pintype "unspecified"))
      (node (ref "U26") (pin "2") (pinfunction "2_2") (pintype "unspecified"))
      (node (ref "U26") (pin "4") (pinfunction "4_4") (pintype "unspecified"))
      (node (ref "U26") (pin "6") (pinfunction "6_6") (pintype "unspecified"))
      (node (ref "U26") (pin "8") (pinfunction "8_8") (pintype "unspecified"))
      (node (ref "U29") (pin "1") (pinfunction "1_1") (pintype "unspecified"))
      (node (ref "U3") (pin "2") (pinfunction "GND_2") (pintype "unspecified"))
      (node (ref "U5") (pin "2") (pinfunction "2_2") (pintype "unspecified"))
      (node (ref "U5") (pin "4") (pinfunction "4_4") (pintype "unspecified"))
      (node (ref "U5") (pin "6") (pinfunction "6_6") (pintype "unspecified"))
      (node (ref "U5") (pin "8") (pinfunction "8_8") (pintype "unspecified"))
      (node (ref "U6") (pin "2") (pinfunction "2_2") (pintype "unspecified"))
      (node (ref "U6") (pin "4") (pinfunction "4_4") (pintype "unspecified"))
      (node (ref "U6") (pin "6") (pinfunction "6_6") (pintype "unspecified"))
      (node (ref "U6") (pin "8") (pinfunction "8_8") (pintype "unspecified"))
      (node (ref "hole1") (pin "1") (pinfunction "GND_1") (pintype "input"))
      (node (ref "hole2") (pin "1") (pinfunction "GND_1") (pintype "input"))
      (node (ref "hole3") (pin "1") (pinfunction "GND_1") (pintype "input"))
      (node (ref "hole4") (pin "1") (pinfunction "GND_1") (pintype "input"))
    )
    (net (code "6") (name "NRST") (class "Default")
      (node (ref "U22") (pin "35") (pinfunction "35_35") (pintype "unspecified"))
      (node (ref "U24") (pin "35") (pinfunction "35_35") (pintype "unspecified"))
    )
    (net (code "7") (name "Net-(BUZZER2-+)") (class "Default")
      (node (ref "BUZZER2") (pin "1") (pinfunction "+_1") (pintype "unspecified"))
      (node (ref "R6") (pin "2") (pinfunction "2_2") (pintype "input"))
    )
    (net (code "8") (name "Net-(BUZZER2--)") (class "Default")
      (node (ref "BUZZER2") (pin "2") (pinfunction "-_2") (pintype "unspecified"))
      (node (ref "Q1") (pin "3") (pinfunction "C_3") (pintype "unspecified"))
    )
    (net (code "9") (name "Net-(C15-Pad2)") (class "Default")
      (node (ref "C15") (pin "2") (pinfunction "2_2") (pintype "input"))
      (node (ref "R5") (pin "1") (pinfunction "1_1") (pintype "input"))
    )
    (net (code "10") (name "Net-(LED1-+)") (class "Default")
      (node (ref "LED1") (pin "2") (pinfunction "+_2") (pintype "unspecified"))
      (node (ref "R2") (pin "1") (pinfunction "1_1") (pintype "input"))
    )
    (net (code "11") (name "Net-(LED2-+)") (class "Default")
      (node (ref "LED2") (pin "2") (pinfunction "+_2") (pintype "unspecified"))
      (node (ref "R3") (pin "1") (pinfunction "1_1") (pintype "input"))
    )
    (net (code "12") (name "Net-(LED5-Pad1)") (class "Default")
      (node (ref "LED5") (pin "1") (pinfunction "1_1") (pintype "unspecified"))
      (node (ref "R31") (pin "2") (pinfunction "2_2") (pintype "input"))
    )
    (net (code "13") (name "Net-(Q1-B)") (class "Default")
      (node (ref "Q1") (pin "1") (pinfunction "B_1") (pintype "unspecified"))
      (node (ref "R7") (pin "1") (pinfunction "1_1") (pintype "input"))
    )
    (net (code "14") (name "Net-(Q2-B)") (class "Default")
      (node (ref "Q2") (pin "1") (pinfunction "B_1") (pintype "unspecified"))
      (node (ref "R32") (pin "1") (pinfunction "1_1") (pintype "input"))
    )
    (net (code "15") (name "Net-(Q2-C)") (class "Default")
      (node (ref "LED5") (pin "2") (pinfunction "2_2") (pintype "unspecified"))
      (node (ref "Q2") (pin "3") (pinfunction "C_3") (pintype "unspecified"))
    )
    (net (code "16") (name "Net-(SW3-Pad5)") (class "Default")
      (node (ref "SW3") (pin "5") (pinfunction "5_5") (pintype "unspecified"))
      (node (ref "U26") (pin "7") (pinfunction "7_7") (pintype "unspecified"))
    )
    (net (code "17") (name "Net-(SW3-Pad6)") (class "Default")
      (node (ref "SW3") (pin "6") (pinfunction "6_6") (pintype "unspecified"))
      (node (ref "U26") (pin "5") (pinfunction "5_5") (pintype "unspecified"))
    )
    (net (code "18") (name "Net-(SW3-Pad7)") (class "Default")
      (node (ref "SW3") (pin "7") (pinfunction "7_7") (pintype "unspecified"))
      (node (ref "U26") (pin "3") (pinfunction "3_3") (pintype "unspecified"))
    )
    (net (code "19") (name "Net-(SW3-Pad8)") (class "Default")
      (node (ref "SW3") (pin "8") (pinfunction "8_8") (pintype "unspecified"))
      (node (ref "U26") (pin "1") (pinfunction "1_1") (pintype "unspecified"))
    )
    (net (code "20") (name "Net-(U2-BOOT)") (class "Default")
      (node (ref "C1") (pin "1") (pinfunction "1_1") (pintype "input"))
      (node (ref "U2") (pin "1") (pinfunction "BOOT_1") (pintype "unspecified"))
    )
    (net (code "21") (name "Net-(U2-COMP)") (class "Default")
      (node (ref "C14") (pin "2") (pinfunction "2_2") (pintype "input"))
      (node (ref "R5") (pin "2") (pinfunction "2_2") (pintype "input"))
      (node (ref "U2") (pin "6") (pinfunction "COMP_6") (pintype "unspecified"))
    )
    (net (code "22") (name "Net-(U2-PH)") (class "Default")
      (node (ref "C1") (pin "2") (pinfunction "2_2") (pintype "input"))
      (node (ref "D1") (pin "1") (pinfunction "1_1") (pintype "unspecified"))
      (node (ref "L1") (pin "1") (pinfunction "1_1") (pintype "unspecified"))
      (node (ref "U2") (pin "8") (pinfunction "PH_8") (pintype "unspecified"))
    )
    (net (code "23") (name "Net-(U2-SS)") (class "Default")
      (node (ref "C13") (pin "2") (pinfunction "2_2") (pintype "input"))
      (node (ref "U2") (pin "4") (pinfunction "SS_4") (pintype "unspecified"))
    )
    (net (code "24") (name "Net-(U2-VSENSE)") (class "Default")
      (node (ref "R1") (pin "1") (pinfunction "1_1") (pintype "input"))
      (node (ref "R4") (pin "2") (pinfunction "2_2") (pintype "input"))
      (node (ref "U2") (pin "5") (pinfunction "VSENSE_5") (pintype "unspecified"))
    )
    (net (code "25") (name "PA0") (class "Default")
      (node (ref "H15") (pin "3") (pinfunction "3_3") (pintype "unspecified"))
      (node (ref "U21") (pin "3") (pinfunction "3_3") (pintype "unspecified"))
      (node (ref "U23") (pin "3") (pinfunction "3_3") (pintype "unspecified"))
    )
    (net (code "26") (name "PA1") (class "Default")
      (node (ref "H15") (pin "4") (pinfunction "4_4") (pintype "unspecified"))
      (node (ref "U21") (pin "5") (pinfunction "5_5") (pintype "unspecified"))
      (node (ref "U23") (pin "5") (pinfunction "5_5") (pintype "unspecified"))
    )
    (net (code "27") (name "PA2{slash}ROSC") (class "Default")
      (node (ref "U22") (pin "19") (pinfunction "19_19") (pintype "unspecified"))
      (node (ref "U24") (pin "19") (pinfunction "19_19") (pintype "unspecified"))
    )
    (net (code "28") (name "PA7") (class "Default")
      (node (ref "H10") (pin "7") (pinfunction "7_7") (pintype "unspecified"))
      (node (ref "U22") (pin "32") (pinfunction "32_32") (pintype "unspecified"))
      (node (ref "U24") (pin "32") (pinfunction "32_32") (pintype "unspecified"))
    )
    (net (code "29") (name "PA8") (class "Default")
      (node (ref "U21") (pin "7") (pinfunction "7_7") (pintype "unspecified"))
      (node (ref "U23") (pin "7") (pinfunction "7_7") (pintype "unspecified"))
    )
    (net (code "30") (name "PA9") (class "Default")
      (node (ref "H2") (pin "2") (pinfunction "2_2") (pintype "unspecified"))
      (node (ref "U21") (pin "9") (pinfunction "9_9") (pintype "unspecified"))
      (node (ref "U23") (pin "9") (pinfunction "9_9") (pintype "unspecified"))
    )
    (net (code "31") (name "PA10{slash}U0TX") (class "Default")
      (node (ref "P4") (pin "5") (pinfunction "5_5") (pintype "unspecified"))
      (node (ref "U21") (pin "12") (pinfunction "12_12") (pintype "unspecified"))
      (node (ref "U23") (pin "12") (pinfunction "12_12") (pintype "unspecified"))
    )
    (net (code "32") (name "PA11{slash}U0RX") (class "Default")
      (node (ref "P4") (pin "4") (pinfunction "4_4") (pintype "unspecified"))
      (node (ref "U21") (pin "14") (pinfunction "14_14") (pintype "unspecified"))
      (node (ref "U23") (pin "14") (pinfunction "14_14") (pintype "unspecified"))
    )
    (net (code "33") (name "PA12") (class "Default")
      (node (ref "U21") (pin "29") (pinfunction "29_29") (pintype "unspecified"))
      (node (ref "U23") (pin "29") (pinfunction "29_29") (pintype "unspecified"))
    )
    (net (code "34") (name "PA13") (class "Default")
      (node (ref "H13") (pin "3") (pinfunction "3_3") (pintype "unspecified"))
      (node (ref "U21") (pin "30") (pinfunction "30_30") (pintype "unspecified"))
      (node (ref "U23") (pin "30") (pinfunction "30_30") (pintype "unspecified"))
    )
    (net (code "35") (name "PA14") (class "Default")
      (node (ref "H13") (pin "2") (pinfunction "2_2") (pintype "unspecified"))
      (node (ref "U22") (pin "11") (pinfunction "11_11") (pintype "unspecified"))
      (node (ref "U24") (pin "11") (pinfunction "11_11") (pintype "unspecified"))
    )
    (net (code "36") (name "PA15") (class "Default")
      (node (ref "U22") (pin "12") (pinfunction "12_12") (pintype "unspecified"))
      (node (ref "U24") (pin "12") (pinfunction "12_12") (pintype "unspecified"))
      (node (ref "U25") (pin "1") (pinfunction "1_1") (pintype "unspecified"))
    )
    (net (code "37") (name "PA16") (class "Default")
      (node (ref "H10") (pin "5") (pinfunction "5_5") (pintype "unspecified"))
      (node (ref "U22") (pin "13") (pinfunction "13_13") (pintype "unspecified"))
      (node (ref "U24") (pin "13") (pinfunction "13_13") (pintype "unspecified"))
    )
    (net (code "38") (name "PA17") (class "Default")
      (node (ref "H2") (pin "3") (pinfunction "3_3") (pintype "unspecified"))
      (node (ref "U22") (pin "14") (pinfunction "14_14") (pintype "unspecified"))
      (node (ref "U24") (pin "14") (pinfunction "14_14") (pintype "unspecified"))
    )
    (net (code "39") (name "PA18{slash}BSL") (class "Default")
      (node (ref "U22") (pin "36") (pinfunction "36_36") (pintype "unspecified"))
      (node (ref "U24") (pin "36") (pinfunction "36_36") (pintype "unspecified"))
    )
    (net (code "40") (name "PA19{slash}SWDIO") (class "Default")
      (node (ref "U21") (pin "19") (pinfunction "19_19") (pintype "unspecified"))
      (node (ref "U23") (pin "19") (pinfunction "19_19") (pintype "unspecified"))
      (node (ref "U29") (pin "3") (pinfunction "3_3") (pintype "unspecified"))
    )
    (net (code "41") (name "PA20{slash}SWCLK") (class "Default")
      (node (ref "U21") (pin "20") (pinfunction "20_20") (pintype "unspecified"))
      (node (ref "U23") (pin "20") (pinfunction "20_20") (pintype "unspecified"))
      (node (ref "U29") (pin "2") (pinfunction "2_2") (pintype "unspecified"))
    )
    (net (code "42") (name "PA21{slash}VREF-") (class "Default")
      (node (ref "U22") (pin "18") (pinfunction "18_18") (pintype "unspecified"))
      (node (ref "U24") (pin "18") (pinfunction "18_18") (pintype "unspecified"))
    )
    (net (code "43") (name "PA22") (class "Default")
      (node (ref "U22") (pin "10") (pinfunction "10_10") (pintype "unspecified"))
      (node (ref "U24") (pin "10") (pinfunction "10_10") (pintype "unspecified"))
    )
    (net (code "44") (name "PA24") (class "Default")
      (node (ref "H10") (pin "1") (pinfunction "1_1") (pintype "unspecified"))
      (node (ref "U22") (pin "6") (pinfunction "6_6") (pintype "unspecified"))
      (node (ref "U24") (pin "6") (pinfunction "6_6") (pintype "unspecified"))
    )
    (net (code "45") (name "PA25") (class "Default")
      (node (ref "U22") (pin "5") (pinfunction "5_5") (pintype "unspecified"))
      (node (ref "U24") (pin "5") (pinfunction "5_5") (pintype "unspecified"))
    )
    (net (code "46") (name "PA26") (class "Default")
      (node (ref "U22") (pin "4") (pinfunction "4_4") (pintype "unspecified"))
      (node (ref "U24") (pin "4") (pinfunction "4_4") (pintype "unspecified"))
    )
    (net (code "47") (name "PA27") (class "Default")
      (node (ref "H8") (pin "6") (pinfunction "6_6") (pintype "unspecified"))
      (node (ref "U22") (pin "3") (pinfunction "3_3") (pintype "unspecified"))
      (node (ref "U24") (pin "3") (pinfunction "3_3") (pintype "unspecified"))
    )
    (net (code "48") (name "PA28") (class "Default")
      (node (ref "U21") (pin "4") (pinfunction "4_4") (pintype "unspecified"))
      (node (ref "U23") (pin "4") (pinfunction "4_4") (pintype "unspecified"))
    )
    (net (code "49") (name "PA29") (class "Default")
      (node (ref "U21") (pin "34") (pinfunction "34_34") (pintype "unspecified"))
      (node (ref "U23") (pin "34") (pinfunction "34_34") (pintype "unspecified"))
    )
    (net (code "50") (name "PA30") (class "Default")
      (node (ref "U22") (pin "27") (pinfunction "27_27") (pintype "unspecified"))
      (node (ref "U24") (pin "27") (pinfunction "27_27") (pintype "unspecified"))
    )
    (net (code "51") (name "PA31") (class "Default")
      (node (ref "U21") (pin "6") (pinfunction "6_6") (pintype "unspecified"))
      (node (ref "U23") (pin "6") (pinfunction "6_6") (pintype "unspecified"))
    )
    (net (code "52") (name "PB0{slash}SPI1_CS2") (class "Default")
      (node (ref "H10") (pin "2") (pinfunction "2_2") (pintype "unspecified"))
      (node (ref "U22") (pin "29") (pinfunction "29_29") (pintype "unspecified"))
      (node (ref "U24") (pin "29") (pinfunction "29_29") (pintype "unspecified"))
    )
    (net (code "53") (name "PB1{slash}SPI1_CS3") (class "Default")
      (node (ref "H10") (pin "3") (pinfunction "3_3") (pintype "unspecified"))
      (node (ref "U22") (pin "30") (pinfunction "30_30") (pintype "unspecified"))
      (node (ref "U24") (pin "30") (pinfunction "30_30") (pintype "unspecified"))
    )
    (net (code "54") (name "PB2") (class "Default")
      (node (ref "U21") (pin "15") (pinfunction "15_15") (pintype "unspecified"))
      (node (ref "U23") (pin "15") (pinfunction "15_15") (pintype "unspecified"))
    )
    (net (code "55") (name "PB3") (class "Default")
      (node (ref "U21") (pin "17") (pinfunction "17_17") (pintype "unspecified"))
      (node (ref "U23") (pin "17") (pinfunction "17_17") (pintype "unspecified"))
    )
    (net (code "56") (name "PB4") (class "Default")
      (node (ref "U21") (pin "8") (pinfunction "8_8") (pintype "unspecified"))
      (node (ref "U23") (pin "8") (pinfunction "8_8") (pintype "unspecified"))
    )
    (net (code "57") (name "PB5") (class "Default")
      (node (ref "U21") (pin "10") (pinfunction "10_10") (pintype "unspecified"))
      (node (ref "U23") (pin "10") (pinfunction "10_10") (pintype "unspecified"))
    )
    (net (code "58") (name "PB6") (class "Default")
      (node (ref "U21") (pin "25") (pinfunction "25_25") (pintype "unspecified"))
      (node (ref "U23") (pin "25") (pinfunction "25_25") (pintype "unspecified"))
    )
    (net (code "59") (name "PB7") (class "Default")
      (node (ref "U21") (pin "26") (pinfunction "26_26") (pintype "unspecified"))
      (node (ref "U23") (pin "26") (pinfunction "26_26") (pintype "unspecified"))
    )
    (net (code "60") (name "PB8") (class "Default")
      (node (ref "H16") (pin "2") (pinfunction "2_2") (pintype "unspecified"))
      (node (ref "U21") (pin "27") (pinfunction "27_27") (pintype "unspecified"))
      (node (ref "U23") (pin "27") (pinfunction "27_27") (pintype "unspecified"))
    )
    (net (code "61") (name "PB9") (class "Default")
      (node (ref "H16") (pin "3") (pinfunction "3_3") (pintype "unspecified"))
      (node (ref "U21") (pin "28") (pinfunction "28_28") (pintype "unspecified"))
      (node (ref "U23") (pin "28") (pinfunction "28_28") (pintype "unspecified"))
    )
    (net (code "62") (name "PB10") (class "Default")
      (node (ref "U22") (pin "31") (pinfunction "31_31") (pintype "unspecified"))
      (node (ref "U24") (pin "31") (pinfunction "31_31") (pintype "unspecified"))
    )
    (net (code "63") (name "PB11") (class "Default")
      (node (ref "H9") (pin "3") (pinfunction "3_3") (pintype "unspecified"))
      (node (ref "U22") (pin "33") (pinfunction "33_33") (pintype "unspecified"))
      (node (ref "U24") (pin "33") (pinfunction "33_33") (pintype "unspecified"))
    )
    (net (code "64") (name "PB12") (class "Default")
      (node (ref "U21") (pin "16") (pinfunction "16_16") (pintype "unspecified"))
      (node (ref "U23") (pin "16") (pinfunction "16_16") (pintype "unspecified"))
    )
    (net (code "65") (name "PB13") (class "Default")
      (node (ref "U21") (pin "18") (pinfunction "18_18") (pintype "unspecified"))
      (node (ref "U23") (pin "18") (pinfunction "18_18") (pintype "unspecified"))
    )
    (net (code "66") (name "PB14") (class "Default")
      (node (ref "H10") (pin "4") (pinfunction "4_4") (pintype "unspecified"))
      (node (ref "U22") (pin "34") (pinfunction "34_34") (pintype "unspecified"))
      (node (ref "U24") (pin "34") (pinfunction "34_34") (pintype "unspecified"))
    )
    (net (code "67") (name "PB15") (class "Default")
      (node (ref "P5") (pin "3") (pinfunction "3_3") (pintype "unspecified"))
      (node (ref "U21") (pin "11") (pinfunction "11_11") (pintype "unspecified"))
      (node (ref "U23") (pin "11") (pinfunction "11_11") (pintype "unspecified"))
    )
    (net (code "68") (name "PB16") (class "Default")
      (node (ref "P5") (pin "4") (pinfunction "4_4") (pintype "unspecified"))
      (node (ref "U21") (pin "13") (pinfunction "13_13") (pintype "unspecified"))
      (node (ref "U23") (pin "13") (pinfunction "13_13") (pintype "unspecified"))
    )
    (net (code "69") (name "PB17") (class "Default")
      (node (ref "H9") (pin "2") (pinfunction "2_2") (pintype "unspecified"))
      (node (ref "U22") (pin "15") (pinfunction "15_15") (pintype "unspecified"))
      (node (ref "U24") (pin "15") (pinfunction "15_15") (pintype "unspecified"))
    )
    (net (code "70") (name "PB18") (class "Default")
      (node (ref "H9") (pin "1") (pinfunction "1_1") (pintype "unspecified"))
      (node (ref "U22") (pin "16") (pinfunction "16_16") (pintype "unspecified"))
      (node (ref "U24") (pin "16") (pinfunction "16_16") (pintype "unspecified"))
    )
    (net (code "71") (name "PB19") (class "Default")
      (node (ref "H10") (pin "6") (pinfunction "6_6") (pintype "unspecified"))
      (node (ref "U22") (pin "17") (pinfunction "17_17") (pintype "unspecified"))
      (node (ref "U24") (pin "17") (pinfunction "17_17") (pintype "unspecified"))
    )
    (net (code "72") (name "PB20") (class "Default")
      (node (ref "U22") (pin "9") (pinfunction "9_9") (pintype "unspecified"))
      (node (ref "U24") (pin "9") (pinfunction "9_9") (pintype "unspecified"))
    )
    (net (code "73") (name "PB21") (class "Default")
      (node (ref "H9") (pin "4") (pinfunction "4_4") (pintype "unspecified"))
      (node (ref "U22") (pin "25") (pinfunction "25_25") (pintype "unspecified"))
      (node (ref "U24") (pin "25") (pinfunction "25_25") (pintype "unspecified"))
    )
    (net (code "74") (name "PB22") (class "Default")
      (node (ref "R29") (pin "2") (pinfunction "2_2") (pintype "input"))
      (node (ref "R32") (pin "2") (pinfunction "2_2") (pintype "input"))
      (node (ref "R7") (pin "2") (pinfunction "2_2") (pintype "input"))
      (node (ref "R8") (pin "2") (pinfunction "2_2") (pintype "input"))
      (node (ref "U22") (pin "26") (pinfunction "26_26") (pintype "unspecified"))
      (node (ref "U24") (pin "26") (pinfunction "26_26") (pintype "unspecified"))
    )
    (net (code "75") (name "PB23") (class "Default")
      (node (ref "H8") (pin "2") (pinfunction "2_2") (pintype "unspecified"))
      (node (ref "U21") (pin "31") (pinfunction "31_31") (pintype "unspecified"))
      (node (ref "U23") (pin "31") (pinfunction "31_31") (pintype "unspecified"))
    )
    (net (code "76") (name "PB24") (class "Default")
      (node (ref "U22") (pin "8") (pinfunction "8_8") (pintype "unspecified"))
      (node (ref "U24") (pin "8") (pinfunction "8_8") (pintype "unspecified"))
    )
    (net (code "77") (name "PB25") (class "Default")
      (node (ref "U22") (pin "7") (pinfunction "7_7") (pintype "unspecified"))
      (node (ref "U24") (pin "7") (pinfunction "7_7") (pintype "unspecified"))
    )
    (net (code "78") (name "PB26") (class "Default")
      (node (ref "H8") (pin "3") (pinfunction "3_3") (pintype "unspecified"))
      (node (ref "U21") (pin "32") (pinfunction "32_32") (pintype "unspecified"))
      (node (ref "U23") (pin "32") (pinfunction "32_32") (pintype "unspecified"))
    )
    (net (code "79") (name "PB27") (class "Default")
      (node (ref "H8") (pin "4") (pinfunction "4_4") (pintype "unspecified"))
      (node (ref "U21") (pin "33") (pinfunction "33_33") (pintype "unspecified"))
      (node (ref "U23") (pin "33") (pinfunction "33_33") (pintype "unspecified"))
    )
    (net (code "80") (name "VBAT") (class "Default")
      (node (ref "P2") (pin "1") (pinfunction "1_1") (pintype "unspecified"))
      (node (ref "U1") (pin "2") (pinfunction "2_2") (pintype "unspecified"))
    )
    (net (code "81") (name "VIN") (class "Default")
      (node (ref "C2") (pin "1") (pinfunction "1_1") (pintype "input"))
      (node (ref "C3") (pin "1") (pinfunction "1_1") (pintype "input"))
      (node (ref "C4") (pin "2") (pinfunction "2_2") (pintype "input"))
      (node (ref "C5") (pin "2") (pinfunction "2_2") (pintype "input"))
      (node (ref "P1") (pin "1") (pinfunction "1_1") (pintype "unspecified"))
      (node (ref "P3") (pin "1") (pinfunction "1_1") (pintype "unspecified"))
      (node (ref "U1") (pin "3") (pinfunction "3_3") (pintype "unspecified"))
      (node (ref "U2") (pin "2") (pinfunction "VIN_2") (pintype "unspecified"))
    )
    (net (code "82") (name "unconnected-(H8-Pad1)") (class "Default")
      (node (ref "H8") (pin "1") (pinfunction "1_1") (pintype "unspecified+no_connect"))
    )
    (net (code "83") (name "unconnected-(H8-Pad5)") (class "Default")
      (node (ref "H8") (pin "5") (pinfunction "5_5") (pintype "unspecified+no_connect"))
    )
    (net (code "84") (name "unconnected-(H9-Pad5)") (class "Default")
      (node (ref "H9") (pin "5") (pinfunction "5_5") (pintype "unspecified+no_connect"))
    )
    (net (code "85") (name "unconnected-(LED5-Pad3)") (class "Default")
      (node (ref "LED5") (pin "3") (pinfunction "3_3") (pintype "unspecified+no_connect"))
    )
    (net (code "86") (name "unconnected-(P4-Pad1)") (class "Default")
      (node (ref "P4") (pin "1") (pinfunction "1_1") (pintype "unspecified+no_connect"))
    )
    (net (code "87") (name "unconnected-(P4-Pad6)") (class "Default")
      (node (ref "P4") (pin "6") (pinfunction "6_6") (pintype "unspecified+no_connect"))
    )
    (net (code "88") (name "unconnected-(P5-Pad1)") (class "Default")
      (node (ref "P5") (pin "1") (pinfunction "1_1") (pintype "unspecified+no_connect"))
    )
    (net (code "89") (name "unconnected-(P5-Pad6)") (class "Default")
      (node (ref "P5") (pin "6") (pinfunction "6_6") (pintype "unspecified+no_connect"))
    )
    (net (code "90") (name "unconnected-(U1-Pad1)") (class "Default")
      (node (ref "U1") (pin "1") (pinfunction "1_1") (pintype "unspecified+no_connect"))
    )
    (net (code "91") (name "unconnected-(U2-EN-Pad3)") (class "Default")
      (node (ref "U2") (pin "3") (pinfunction "EN_3") (pintype "unspecified+no_connect"))
    )
    (net (code "92") (name "unconnected-(U3-NC-Pad4)") (class "Default")
      (node (ref "U3") (pin "4") (pinfunction "NC_4") (pintype "unspecified+no_connect"))
    )
    (net (code "93") (name "unconnected-(U29-Pad5)") (class "Default")
      (node (ref "U29") (pin "5") (pinfunction "5_5") (pintype "unspecified+no_connect"))
    )
  )
)
